# pmu.net
KiCad netlist of a schematic drawn in Altium Designer
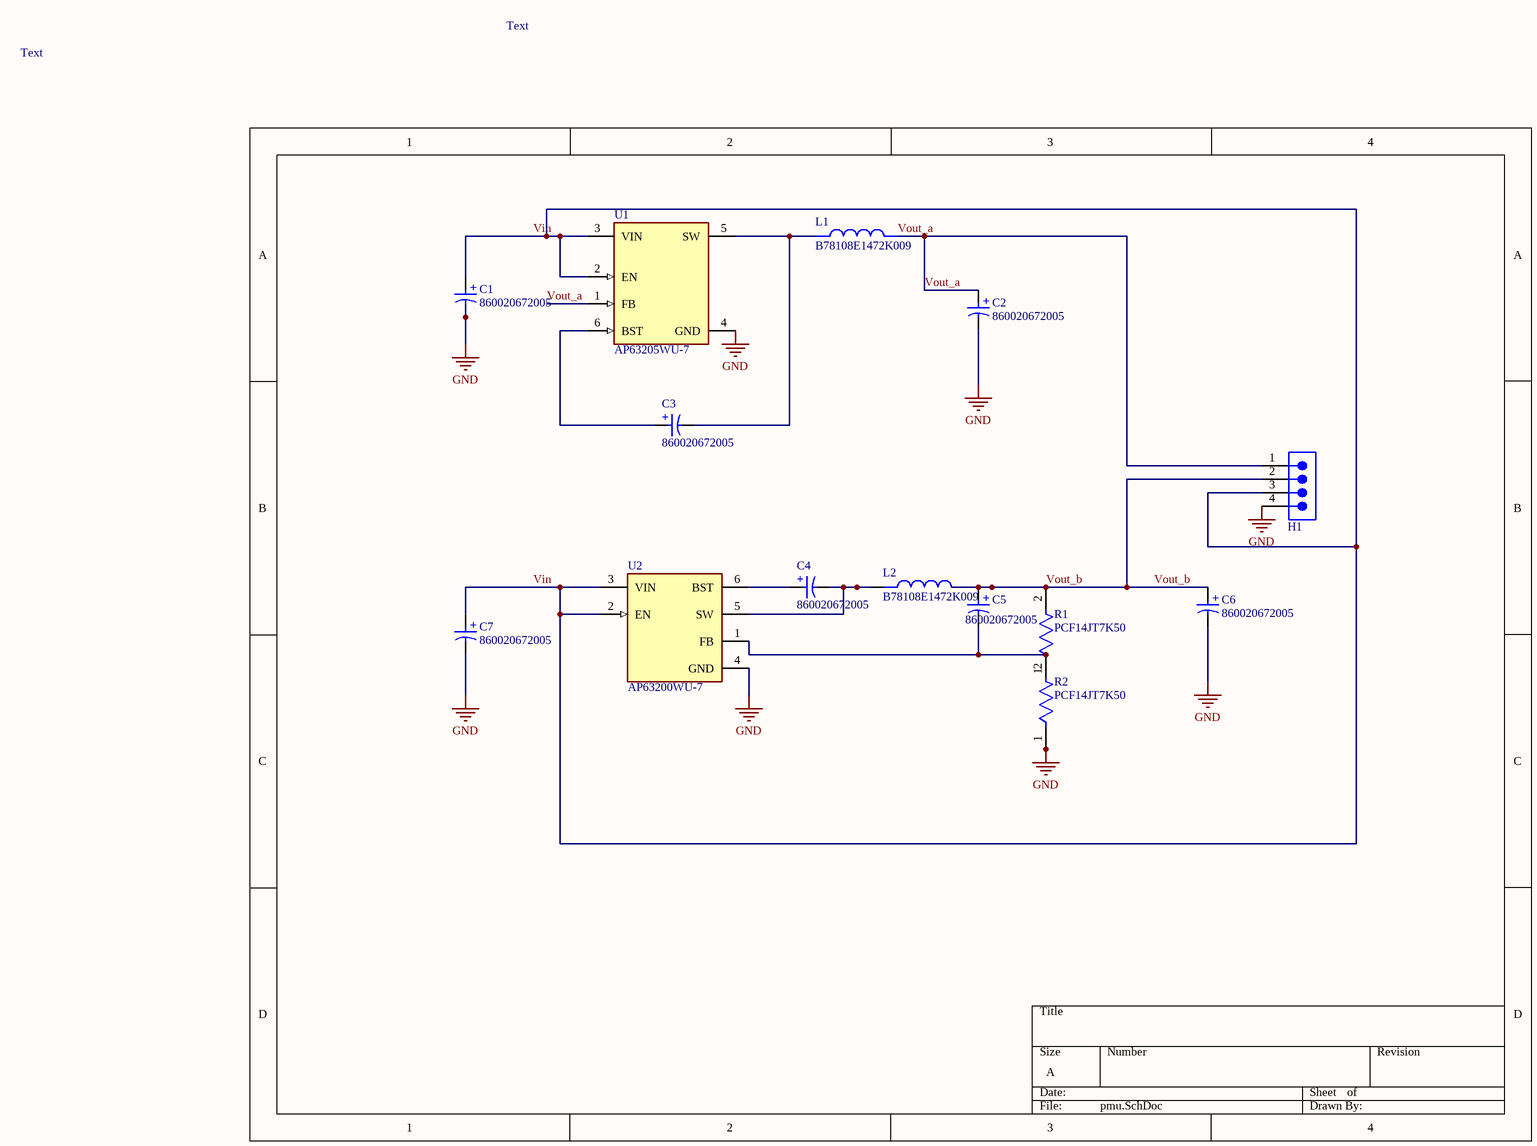
[diagram p0: pmu.SchDoc]

(export (version "E")
  (design (tool "Eeschema 10.0.6"))
  (components
    (comp (ref "C1")
      (value "860020672005")
      (footprint "WCAP-ATG5_D5H11")
      (description "860020672005 WCAP-ATG5 Aluminum Electrolytic Capacitors")
      (fields (field (name "TOLERANCE") "20%"))
      (libsource (lib "Altium Content Vault") (part "Capacitor_Polarized"))
    )
    (comp (ref "C2")
      (value "860020672005")
      (footprint "WCAP-ATG5_D5H11")
      (description "860020672005 WCAP-ATG5 Aluminum Electrolytic Capacitors")
      (fields (field (name "TOLERANCE") "20%"))
      (libsource (lib "Altium Content Vault") (part "Capacitor_Polarized"))
    )
    (comp (ref "C3")
      (value "860020672005")
      (footprint "WCAP-ATG5_D5H11")
      (description "860020672005 WCAP-ATG5 Aluminum Electrolytic Capacitors")
      (fields (field (name "TOLERANCE") "20%"))
      (libsource (lib "Altium Content Vault") (part "Capacitor_Polarized"))
    )
    (comp (ref "C4")
      (value "860020672005")
      (footprint "WCAP-ATG5_D5H11")
      (description "860020672005 WCAP-ATG5 Aluminum Electrolytic Capacitors")
      (fields (field (name "TOLERANCE") "20%"))
      (libsource (lib "Altium Content Vault") (part "Capacitor_Polarized"))
    )
    (comp (ref "C5")
      (value "860020672005")
      (footprint "WCAP-ATG5_D5H11")
      (description "860020672005 WCAP-ATG5 Aluminum Electrolytic Capacitors")
      (fields (field (name "TOLERANCE") "20%"))
      (libsource (lib "Altium Content Vault") (part "Capacitor_Polarized"))
    )
    (comp (ref "C6")
      (value "860020672005")
      (footprint "WCAP-ATG5_D5H11")
      (description "860020672005 WCAP-ATG5 Aluminum Electrolytic Capacitors")
      (fields (field (name "TOLERANCE") "20%"))
      (libsource (lib "Altium Content Vault") (part "Capacitor_Polarized"))
    )
    (comp (ref "C7")
      (value "860020672005")
      (footprint "WCAP-ATG5_D5H11")
      (description "860020672005 WCAP-ATG5 Aluminum Electrolytic Capacitors")
      (fields (field (name "TOLERANCE") "20%"))
      (libsource (lib "Altium Content Vault") (part "Capacitor_Polarized"))
    )
    (comp (ref "H1")
      (value "61300411121")
      (footprint "61300411121")
      (description "WR-PHD Pin Header, THT, Vertical, pitch 2.54mm, 1 Row, 4P")
      (fields (field (name "MANUFACTURER") "Wurth Elektronik"))
      (libsource (lib "pmu") (part "61300411121"))
    )
    (comp (ref "L1")
      (value "B78108E1472K009")
      (footprint "INDAD1430W80L950D400")
      (description "4.7 ÂµH Unshielded Drum Core, Wirewound Inductor 2.75 A 85mOhm Max Axial")
      (fields (field (name "DIGI-KEY_PART_NUMBER") "495-76025-1-ND") (field (name "MF") "EPCOS"))
      (libsource (lib "B78108E1472K009") (part "B78108E1472K009"))
    )
    (comp (ref "L2")
      (value "B78108E1472K009")
      (footprint "INDAD1430W80L950D400")
      (description "4.7 ÂµH Unshielded Drum Core, Wirewound Inductor 2.75 A 85mOhm Max Axial")
      (fields (field (name "DIGI-KEY_PART_NUMBER") "495-76025-1-ND") (field (name "MF") "EPCOS"))
      (libsource (lib "B78108E1472K009") (part "B78108E1472K009"))
    )
    (comp (ref "R1")
      (value "PCF14JT7K50")
      (footprint "FP-CF14-MFG")
      (description "RES 7.5K OHM 1/4W 5% AXIAL")
      (fields (field (name "TOLERANCE") "5%"))
      (libsource (lib "Altium Content Vault") (part "1029c3af85768c4190bb7ad29bc67b5"))
    )
    (comp (ref "R2")
      (value "PCF14JT7K50")
      (footprint "FP-CF14-MFG")
      (description "RES 7.5K OHM 1/4W 5% AXIAL")
      (fields (field (name "TOLERANCE") "5%"))
      (libsource (lib "Altium Content Vault") (part "1029c3af85768c4190bb7ad29bc67b5"))
    )
    (comp (ref "U1")
      (value "AP63205WU-7")
      (footprint "FP-TSOT26-MFG")
      (description "IC REG BUCK 5V 2A TSOT26")
      (fields
        (field (name "MANUFACTURER") "Diodes Inc.")
        (field (name "OCTOPART") "https://octopart.com/ap63205wu-7-diodes+inc.-98099551")
      )
      (libsource (lib "Altium Content Vault") (part "029bc9fbfa4a99dbb8b3a24c2adb655"))
    )
    (comp (ref "U2")
      (value "AP63200WU-7")
      (footprint "FP-TSOT26-MFG")
      (description "IC REG BUCK ADJUSTABLE 2A TSOT26")
      (fields
        (field (name "OCTOPART") "https://octopart.com/ap63200wu-7-diodes+inc.-98099548")
        (field (name "MANUFACTURER") "Diodes Inc.")
      )
      (libsource (lib "Altium Content Vault") (part "2ae3aed49e7ee94ca813948749813a1"))
    )
  )
  (nets
    (net (code "1") (name "/Vin") (class "Default")
      (node (ref "C1") (pin "1") (pinfunction "P_1") (pintype "passive"))
      (node (ref "C7") (pin "1") (pinfunction "P_1") (pintype "passive"))
      (node (ref "H1") (pin "3") (pinfunction "3_3") (pintype "passive"))
      (node (ref "U1") (pin "2") (pinfunction "EN_2") (pintype "input"))
      (node (ref "U1") (pin "3") (pinfunction "VIN_3") (pintype "power_in"))
      (node (ref "U2") (pin "2") (pinfunction "EN_2") (pintype "input"))
      (node (ref "U2") (pin "3") (pinfunction "VIN_3") (pintype "power_in"))
    )
    (net (code "2") (name "/Vout_a") (class "Default")
      (node (ref "C2") (pin "1") (pinfunction "P_1") (pintype "passive"))
      (node (ref "H1") (pin "1") (pinfunction "1_1") (pintype "passive"))
      (node (ref "L1") (pin "2") (pinfunction "2_2") (pintype "passive"))
      (node (ref "U1") (pin "1") (pinfunction "FB_1") (pintype "input"))
    )
    (net (code "3") (name "/Vout_b") (class "Default")
      (node (ref "C5") (pin "1") (pinfunction "P_1") (pintype "passive"))
      (node (ref "C6") (pin "1") (pinfunction "P_1") (pintype "passive"))
      (node (ref "H1") (pin "2") (pinfunction "2_2") (pintype "passive"))
      (node (ref "L2") (pin "2") (pinfunction "2_2") (pintype "passive"))
      (node (ref "R1") (pin "2") (pinfunction "2_2") (pintype "passive"))
    )
    (net (code "4") (name "GND") (class "Default")
      (node (ref "C1") (pin "2") (pinfunction "N_2") (pintype "passive"))
      (node (ref "C2") (pin "2") (pinfunction "N_2") (pintype "passive"))
      (node (ref "C6") (pin "2") (pinfunction "N_2") (pintype "passive"))
      (node (ref "C7") (pin "2") (pinfunction "N_2") (pintype "passive"))
      (node (ref "H1") (pin "4") (pinfunction "4_4") (pintype "passive"))
      (node (ref "R2") (pin "1") (pinfunction "1_1") (pintype "passive"))
      (node (ref "U1") (pin "4") (pinfunction "GND_4") (pintype "power_in"))
      (node (ref "U2") (pin "4") (pinfunction "GND_4") (pintype "power_in"))
    )
    (net (code "5") (name "Net-(C3-N)") (class "Default")
      (node (ref "C3") (pin "2") (pinfunction "N_2") (pintype "passive"))
      (node (ref "L1") (pin "1") (pinfunction "1_1") (pintype "passive"))
      (node (ref "U1") (pin "5") (pinfunction "SW_5") (pintype "power_in"))
    )
    (net (code "6") (name "Net-(C3-P)") (class "Default")
      (node (ref "C3") (pin "1") (pinfunction "P_1") (pintype "passive"))
      (node (ref "U1") (pin "6") (pinfunction "BST_6") (pintype "input"))
    )
    (net (code "7") (name "Net-(C4-N)") (class "Default")
      (node (ref "C4") (pin "2") (pinfunction "N_2") (pintype "passive"))
      (node (ref "L2") (pin "1") (pinfunction "1_1") (pintype "passive"))
      (node (ref "U2") (pin "5") (pinfunction "SW_5") (pintype "passive"))
    )
    (net (code "8") (name "Net-(C4-P)") (class "Default")
      (node (ref "C4") (pin "1") (pinfunction "P_1") (pintype "passive"))
      (node (ref "U2") (pin "6") (pinfunction "BST_6") (pintype "passive"))
    )
    (net (code "9") (name "Net-(C5-N)") (class "Default")
      (node (ref "C5") (pin "2") (pinfunction "N_2") (pintype "passive"))
      (node (ref "R1") (pin "1") (pinfunction "1_1") (pintype "passive"))
      (node (ref "R2") (pin "2") (pinfunction "2_2") (pintype "passive"))
      (node (ref "U2") (pin "1") (pinfunction "FB_1") (pintype "passive"))
    )
  )
)
